# AND_gate.net
KiCad netlist of a schematic drawn in EAGLE
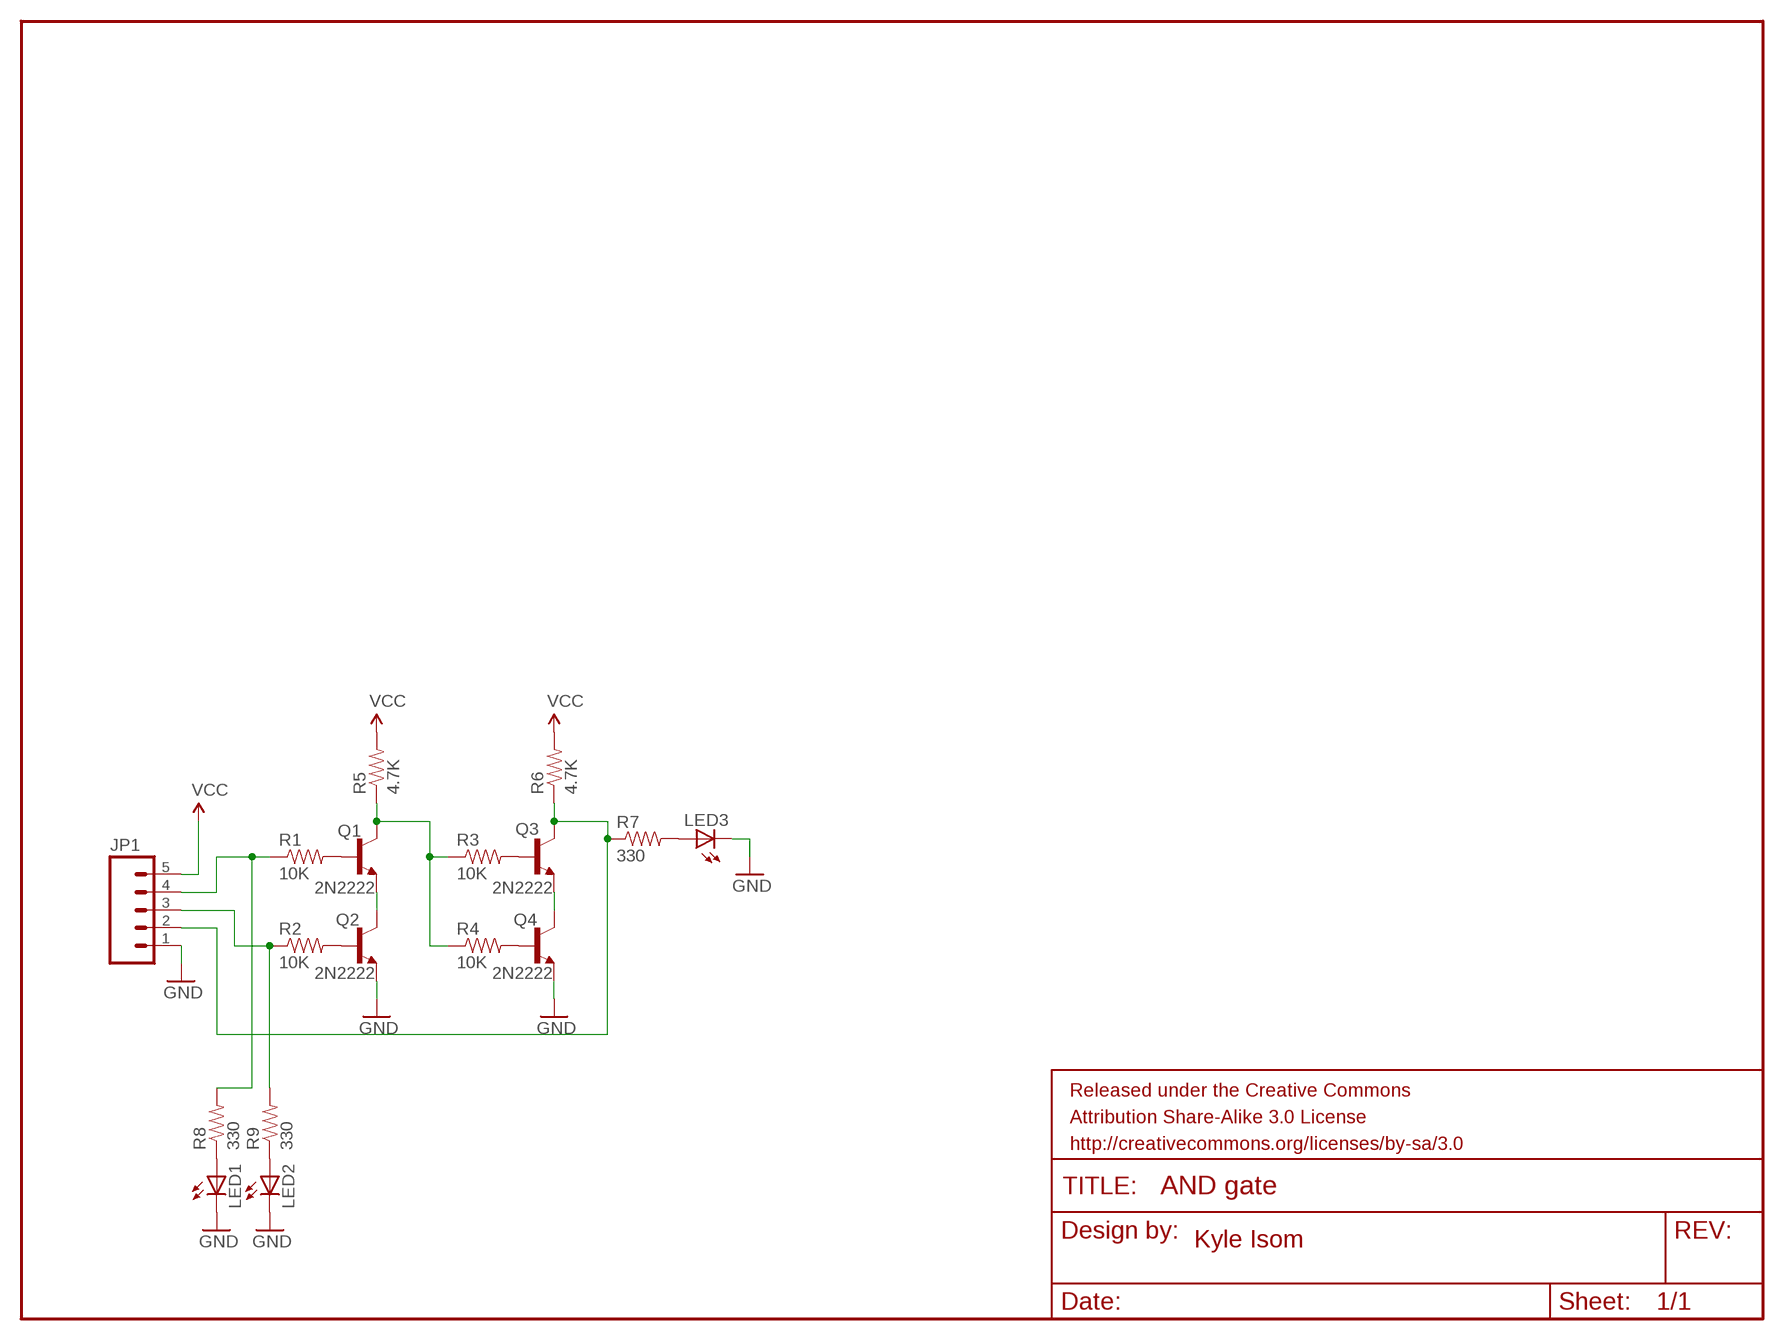
[diagram p0: schematic, sheet 1]

(export (version "E")
  (design (tool "Eeschema 10.0.6"))
  (components
    (comp (ref "FRAME1")
      (value "FRAME-LETTER")
      (footprint "eagle-import:CREATIVE_COMMONS")
      (libsource (lib "eagle-import") (part "FRAME-LETTER"))
    )
    (comp (ref "JP1")
      (value "M05LOCK")
      (footprint "eagle-import:1X05_LOCK")
      (libsource (lib "eagle-import") (part "M05LOCK"))
    )
    (comp (ref "LED1")
      (value "LED3MM")
      (footprint "eagle-import:LED3MM")
      (libsource (lib "eagle-import") (part "LED3MM"))
    )
    (comp (ref "LED2")
      (value "LED3MM")
      (footprint "eagle-import:LED3MM")
      (libsource (lib "eagle-import") (part "LED3MM"))
    )
    (comp (ref "LED3")
      (value "LED3MM")
      (footprint "eagle-import:LED3MM")
      (libsource (lib "eagle-import") (part "LED3MM"))
    )
    (comp (ref "Q1")
      (value "2N2222")
      (footprint "eagle-import:TO-92-AMMO")
      (libsource (lib "eagle-import") (part "TRANSISTOR_NPNTO-92-AMMO"))
    )
    (comp (ref "Q2")
      (value "2N2222")
      (footprint "eagle-import:TO-92-AMMO")
      (libsource (lib "eagle-import") (part "TRANSISTOR_NPNTO-92-AMMO"))
    )
    (comp (ref "Q3")
      (value "2N2222")
      (footprint "eagle-import:TO-92-AMMO")
      (libsource (lib "eagle-import") (part "TRANSISTOR_NPNTO-92-AMMO"))
    )
    (comp (ref "Q4")
      (value "2N2222")
      (footprint "eagle-import:TO-92-AMMO")
      (libsource (lib "eagle-import") (part "TRANSISTOR_NPNTO-92-AMMO"))
    )
    (comp (ref "R1")
      (value "10K")
      (footprint "eagle-import:AXIAL-0.4")
      (libsource (lib "eagle-import") (part "RESISTORPTH-1/4W"))
    )
    (comp (ref "R2")
      (value "10K")
      (footprint "eagle-import:AXIAL-0.4")
      (libsource (lib "eagle-import") (part "RESISTORPTH-1/4W"))
    )
    (comp (ref "R3")
      (value "10K")
      (footprint "eagle-import:AXIAL-0.4")
      (libsource (lib "eagle-import") (part "RESISTORPTH-1/4W"))
    )
    (comp (ref "R4")
      (value "10K")
      (footprint "eagle-import:AXIAL-0.4")
      (libsource (lib "eagle-import") (part "RESISTORPTH-1/4W"))
    )
    (comp (ref "R5")
      (value "4.7K")
      (footprint "eagle-import:AXIAL-0.4")
      (libsource (lib "eagle-import") (part "RESISTORPTH-1/4W"))
    )
    (comp (ref "R6")
      (value "4.7K")
      (footprint "eagle-import:AXIAL-0.4")
      (libsource (lib "eagle-import") (part "RESISTORPTH-1/4W"))
    )
    (comp (ref "R7")
      (value "330")
      (footprint "eagle-import:AXIAL-0.4")
      (libsource (lib "eagle-import") (part "RESISTORPTH-1/4W"))
    )
    (comp (ref "R8")
      (value "330")
      (footprint "eagle-import:AXIAL-0.4")
      (libsource (lib "eagle-import") (part "RESISTORPTH-1/4W"))
    )
    (comp (ref "R9")
      (value "330")
      (footprint "eagle-import:AXIAL-0.4")
      (libsource (lib "eagle-import") (part "RESISTORPTH-1/4W"))
    )
  )
  (nets
    (net (code "1") (name "GND") (class "Default")
      (node (ref "JP1") (pin "1") (pinfunction "1_1") (pintype "passive"))
      (node (ref "LED1") (pin "K") (pinfunction "C_K") (pintype "passive"))
      (node (ref "LED2") (pin "K") (pinfunction "C_K") (pintype "passive"))
      (node (ref "LED3") (pin "K") (pinfunction "C_K") (pintype "passive"))
      (node (ref "Q2") (pin "1") (pinfunction "E_1") (pintype "passive"))
      (node (ref "Q4") (pin "1") (pinfunction "E_1") (pintype "passive"))
    )
    (net (code "2") (name "Net-(Q1-B)") (class "Default")
      (node (ref "Q1") (pin "2") (pinfunction "B_2") (pintype "passive"))
      (node (ref "R1") (pin "P$2") (pinfunction "2_P$2") (pintype "passive"))
    )
    (net (code "3") (name "Net-(Q1-C)") (class "Default")
      (node (ref "Q1") (pin "3") (pinfunction "C_3") (pintype "passive"))
      (node (ref "R3") (pin "P$1") (pinfunction "1_P$1") (pintype "passive"))
      (node (ref "R4") (pin "P$1") (pinfunction "1_P$1") (pintype "passive"))
      (node (ref "R5") (pin "P$1") (pinfunction "1_P$1") (pintype "passive"))
    )
    (net (code "4") (name "Net-(Q1-E)") (class "Default")
      (node (ref "Q1") (pin "1") (pinfunction "E_1") (pintype "passive"))
      (node (ref "Q2") (pin "3") (pinfunction "C_3") (pintype "passive"))
    )
    (net (code "5") (name "Net-(Q2-B)") (class "Default")
      (node (ref "Q2") (pin "2") (pinfunction "B_2") (pintype "passive"))
      (node (ref "R2") (pin "P$2") (pinfunction "2_P$2") (pintype "passive"))
    )
    (net (code "6") (name "Net-(Q3-B)") (class "Default")
      (node (ref "Q3") (pin "2") (pinfunction "B_2") (pintype "passive"))
      (node (ref "R3") (pin "P$2") (pinfunction "2_P$2") (pintype "passive"))
    )
    (net (code "7") (name "Net-(Q3-C)") (class "Default")
      (node (ref "JP1") (pin "2") (pinfunction "2_2") (pintype "passive"))
      (node (ref "Q3") (pin "3") (pinfunction "C_3") (pintype "passive"))
      (node (ref "R6") (pin "P$1") (pinfunction "1_P$1") (pintype "passive"))
      (node (ref "R7") (pin "P$1") (pinfunction "1_P$1") (pintype "passive"))
    )
    (net (code "8") (name "Net-(Q3-E)") (class "Default")
      (node (ref "Q3") (pin "1") (pinfunction "E_1") (pintype "passive"))
      (node (ref "Q4") (pin "3") (pinfunction "C_3") (pintype "passive"))
    )
    (net (code "9") (name "Net-(Q4-B)") (class "Default")
      (node (ref "Q4") (pin "2") (pinfunction "B_2") (pintype "passive"))
      (node (ref "R4") (pin "P$2") (pinfunction "2_P$2") (pintype "passive"))
    )
    (net (code "10") (name "Net-(R1-1)") (class "Default")
      (node (ref "JP1") (pin "4") (pinfunction "4_4") (pintype "passive"))
      (node (ref "R1") (pin "P$1") (pinfunction "1_P$1") (pintype "passive"))
      (node (ref "R8") (pin "P$2") (pinfunction "2_P$2") (pintype "passive"))
    )
    (net (code "11") (name "Net-(R2-1)") (class "Default")
      (node (ref "JP1") (pin "3") (pinfunction "3_3") (pintype "passive"))
      (node (ref "R2") (pin "P$1") (pinfunction "1_P$1") (pintype "passive"))
      (node (ref "R9") (pin "P$2") (pinfunction "2_P$2") (pintype "passive"))
    )
    (net (code "12") (name "Net-(R7-2)") (class "Default")
      (node (ref "LED3") (pin "A") (pinfunction "A_A") (pintype "passive"))
      (node (ref "R7") (pin "P$2") (pinfunction "2_P$2") (pintype "passive"))
    )
    (net (code "13") (name "Net-(R8-1)") (class "Default")
      (node (ref "LED1") (pin "A") (pinfunction "A_A") (pintype "passive"))
      (node (ref "R8") (pin "P$1") (pinfunction "1_P$1") (pintype "passive"))
    )
    (net (code "14") (name "Net-(R9-1)") (class "Default")
      (node (ref "LED2") (pin "A") (pinfunction "A_A") (pintype "passive"))
      (node (ref "R9") (pin "P$1") (pinfunction "1_P$1") (pintype "passive"))
    )
    (net (code "15") (name "VCC") (class "Default")
      (node (ref "JP1") (pin "5") (pinfunction "5_5") (pintype "passive"))
      (node (ref "R5") (pin "P$2") (pinfunction "2_P$2") (pintype "passive"))
      (node (ref "R6") (pin "P$2") (pinfunction "2_P$2") (pintype "passive"))
    )
  )
)
